# driver.net
KiCad netlist of a schematic drawn in EAGLE
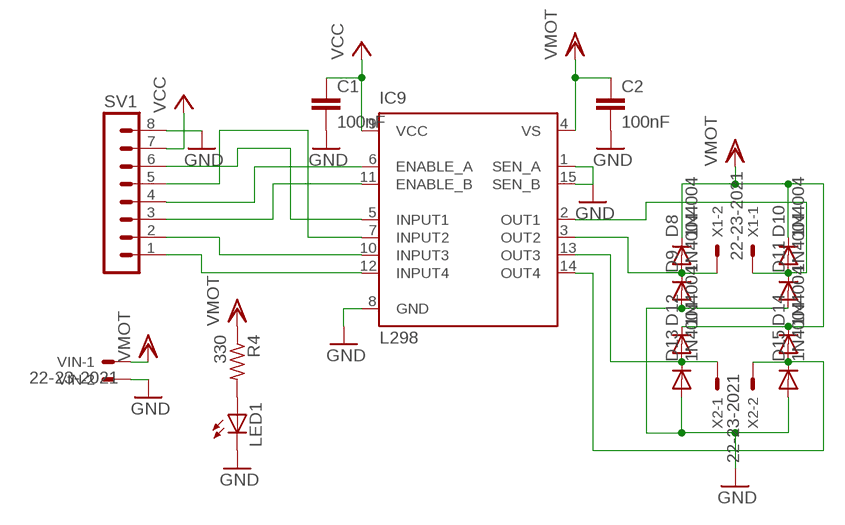
[diagram p0: schematic, sheet 1]

(export (version "E")
  (design (tool "Eeschema 10.0.6"))
  (components
    (comp (ref "C1")
      (value "100nF")
      (footprint "eagle-import:C025-025X050")
      (libsource (lib "eagle-import") (part "C-EU025-025X050"))
    )
    (comp (ref "C2")
      (value "100nF")
      (footprint "eagle-import:C025-025X050")
      (libsource (lib "eagle-import") (part "C-EU025-025X050"))
    )
    (comp (ref "D8")
      (value "1N4004")
      (footprint "eagle-import:DO41-10")
      (libsource (lib "eagle-import") (part "1N4004"))
    )
    (comp (ref "D9")
      (value "1N4004")
      (footprint "eagle-import:DO41-10")
      (libsource (lib "eagle-import") (part "1N4004"))
    )
    (comp (ref "D10")
      (value "1N4004")
      (footprint "eagle-import:DO41-10")
      (libsource (lib "eagle-import") (part "1N4004"))
    )
    (comp (ref "D11")
      (value "1N4004")
      (footprint "eagle-import:DO41-10")
      (libsource (lib "eagle-import") (part "1N4004"))
    )
    (comp (ref "D12")
      (value "1N4004")
      (footprint "eagle-import:DO41-10")
      (libsource (lib "eagle-import") (part "1N4004"))
    )
    (comp (ref "D13")
      (value "1N4004")
      (footprint "eagle-import:DO41-10")
      (libsource (lib "eagle-import") (part "1N4004"))
    )
    (comp (ref "D14")
      (value "1N4004")
      (footprint "eagle-import:DO41-10")
      (libsource (lib "eagle-import") (part "1N4004"))
    )
    (comp (ref "D15")
      (value "1N4004")
      (footprint "eagle-import:DO41-10")
      (libsource (lib "eagle-import") (part "1N4004"))
    )
    (comp (ref "IC9")
      (value "L298")
      (footprint "eagle-import:MULTIWATT-15")
      (libsource (lib "eagle-import") (part "L298"))
    )
    (comp (ref "LED1")
      (value "LED3MM")
      (footprint "eagle-import:LED3MM")
      (libsource (lib "eagle-import") (part "LED3MM"))
    )
    (comp (ref "R4")
      (value "330")
      (footprint "eagle-import:0207_10")
      (libsource (lib "eagle-import") (part "R-US_0207/10"))
    )
    (comp (ref "SV1")
      (value "MA08-1")
      (footprint "eagle-import:MA08-1")
      (libsource (lib "eagle-import") (part "MA08-1"))
    )
    (comp (ref "VIN")
      (value "22-23-2021")
      (footprint "eagle-import:22-23-2021")
      (fields
        (field (name "MF") "MOLEX")
        (field (name "MF_1") "MOLEX")
        (field (name "MPN") "22-23-2021")
        (field (name "OC_FARNELL") "1462926")
        (field (name "OC_NEWARK") "25C3832")
      )
      (libsource (lib "eagle-import") (part "22-23-2021"))
    )
    (comp (ref "X1")
      (value "22-23-2021")
      (footprint "eagle-import:22-23-2021")
      (fields (field (name "MF") "MOLEX"))
      (libsource (lib "eagle-import") (part "22-23-2021"))
    )
    (comp (ref "X2")
      (value "22-23-2021")
      (footprint "eagle-import:22-23-2021")
      (fields (field (name "MF") "MOLEX"))
      (libsource (lib "eagle-import") (part "22-23-2021"))
    )
  )
  (nets
    (net (code "1") (name "GND") (class "Default")
      (node (ref "C1") (pin "2") (pinfunction "2_2") (pintype "passive"))
      (node (ref "C2") (pin "2") (pinfunction "2_2") (pintype "passive"))
      (node (ref "D11") (pin "A") (pinfunction "A_A") (pintype "passive"))
      (node (ref "D13") (pin "A") (pinfunction "A_A") (pintype "passive"))
      (node (ref "D15") (pin "A") (pinfunction "A_A") (pintype "passive"))
      (node (ref "D9") (pin "A") (pinfunction "A_A") (pintype "passive"))
      (node (ref "IC9") (pin "1") (pinfunction "SEN_A_1") (pintype "input"))
      (node (ref "IC9") (pin "15") (pinfunction "SEN_B_15") (pintype "input"))
      (node (ref "IC9") (pin "8") (pinfunction "GND_8") (pintype "power_in"))
      (node (ref "LED1") (pin "K") (pinfunction "C_K") (pintype "passive"))
      (node (ref "SV1") (pin "8") (pinfunction "8_8") (pintype "passive"))
      (node (ref "VIN") (pin "2") (pinfunction "S_2") (pintype "passive"))
    )
    (net (code "2") (name "Net-(IC9-ENABLE_A)") (class "Default")
      (node (ref "IC9") (pin "6") (pinfunction "ENABLE_A_6") (pintype "input"))
      (node (ref "SV1") (pin "4") (pinfunction "4_4") (pintype "passive"))
    )
    (net (code "3") (name "Net-(IC9-ENABLE_B)") (class "Default")
      (node (ref "IC9") (pin "11") (pinfunction "ENABLE_B_11") (pintype "input"))
      (node (ref "SV1") (pin "3") (pinfunction "3_3") (pintype "passive"))
    )
    (net (code "4") (name "Net-(IC9-INPUT1)") (class "Default")
      (node (ref "IC9") (pin "5") (pinfunction "INPUT1_5") (pintype "input"))
      (node (ref "SV1") (pin "6") (pinfunction "6_6") (pintype "passive"))
    )
    (net (code "5") (name "Net-(IC9-INPUT2)") (class "Default")
      (node (ref "IC9") (pin "7") (pinfunction "INPUT2_7") (pintype "input"))
      (node (ref "SV1") (pin "5") (pinfunction "5_5") (pintype "passive"))
    )
    (net (code "6") (name "Net-(IC9-INPUT3)") (class "Default")
      (node (ref "IC9") (pin "10") (pinfunction "INPUT3_10") (pintype "input"))
      (node (ref "SV1") (pin "2") (pinfunction "2_2") (pintype "passive"))
    )
    (net (code "7") (name "Net-(IC9-INPUT4)") (class "Default")
      (node (ref "IC9") (pin "12") (pinfunction "INPUT4_12") (pintype "input"))
      (node (ref "SV1") (pin "1") (pinfunction "1_1") (pintype "passive"))
    )
    (net (code "8") (name "Net-(IC9-OUT1)") (class "Default")
      (node (ref "D10") (pin "A") (pinfunction "A_A") (pintype "passive"))
      (node (ref "D11") (pin "C") (pinfunction "C_C") (pintype "passive"))
      (node (ref "IC9") (pin "2") (pinfunction "OUT1_2") (pintype "output"))
      (node (ref "X1") (pin "1") (pinfunction "S_1") (pintype "passive"))
    )
    (net (code "9") (name "Net-(IC9-OUT2)") (class "Default")
      (node (ref "D8") (pin "A") (pinfunction "A_A") (pintype "passive"))
      (node (ref "D9") (pin "C") (pinfunction "C_C") (pintype "passive"))
      (node (ref "IC9") (pin "3") (pinfunction "OUT2_3") (pintype "output"))
      (node (ref "X1") (pin "2") (pinfunction "S_2") (pintype "passive"))
    )
    (net (code "10") (name "Net-(IC9-OUT3)") (class "Default")
      (node (ref "D12") (pin "A") (pinfunction "A_A") (pintype "passive"))
      (node (ref "D13") (pin "C") (pinfunction "C_C") (pintype "passive"))
      (node (ref "IC9") (pin "13") (pinfunction "OUT3_13") (pintype "output"))
      (node (ref "X2") (pin "1") (pinfunction "S_1") (pintype "passive"))
    )
    (net (code "11") (name "Net-(IC9-OUT4)") (class "Default")
      (node (ref "D14") (pin "A") (pinfunction "A_A") (pintype "passive"))
      (node (ref "D15") (pin "C") (pinfunction "C_C") (pintype "passive"))
      (node (ref "IC9") (pin "14") (pinfunction "OUT4_14") (pintype "output"))
      (node (ref "X2") (pin "2") (pinfunction "S_2") (pintype "passive"))
    )
    (net (code "12") (name "Net-(LED1-PadA)") (class "Default")
      (node (ref "LED1") (pin "A") (pinfunction "A_A") (pintype "passive"))
      (node (ref "R4") (pin "2") (pinfunction "2_2") (pintype "passive"))
    )
    (net (code "13") (name "VCC") (class "Default")
      (node (ref "C1") (pin "1") (pinfunction "1_1") (pintype "passive"))
      (node (ref "IC9") (pin "9") (pinfunction "VCC_9") (pintype "power_in"))
      (node (ref "SV1") (pin "7") (pinfunction "7_7") (pintype "passive"))
    )
    (net (code "14") (name "VMOT") (class "Default")
      (node (ref "C2") (pin "1") (pinfunction "1_1") (pintype "passive"))
      (node (ref "D10") (pin "C") (pinfunction "C_C") (pintype "passive"))
      (node (ref "D12") (pin "C") (pinfunction "C_C") (pintype "passive"))
      (node (ref "D14") (pin "C") (pinfunction "C_C") (pintype "passive"))
      (node (ref "D8") (pin "C") (pinfunction "C_C") (pintype "passive"))
      (node (ref "IC9") (pin "4") (pinfunction "VS_4") (pintype "power_in"))
      (node (ref "R4") (pin "1") (pinfunction "1_1") (pintype "passive"))
      (node (ref "VIN") (pin "1") (pinfunction "S_1") (pintype "passive"))
    )
  )
)
